# MCU.net
KiCad netlist of a schematic drawn in Altium Designer
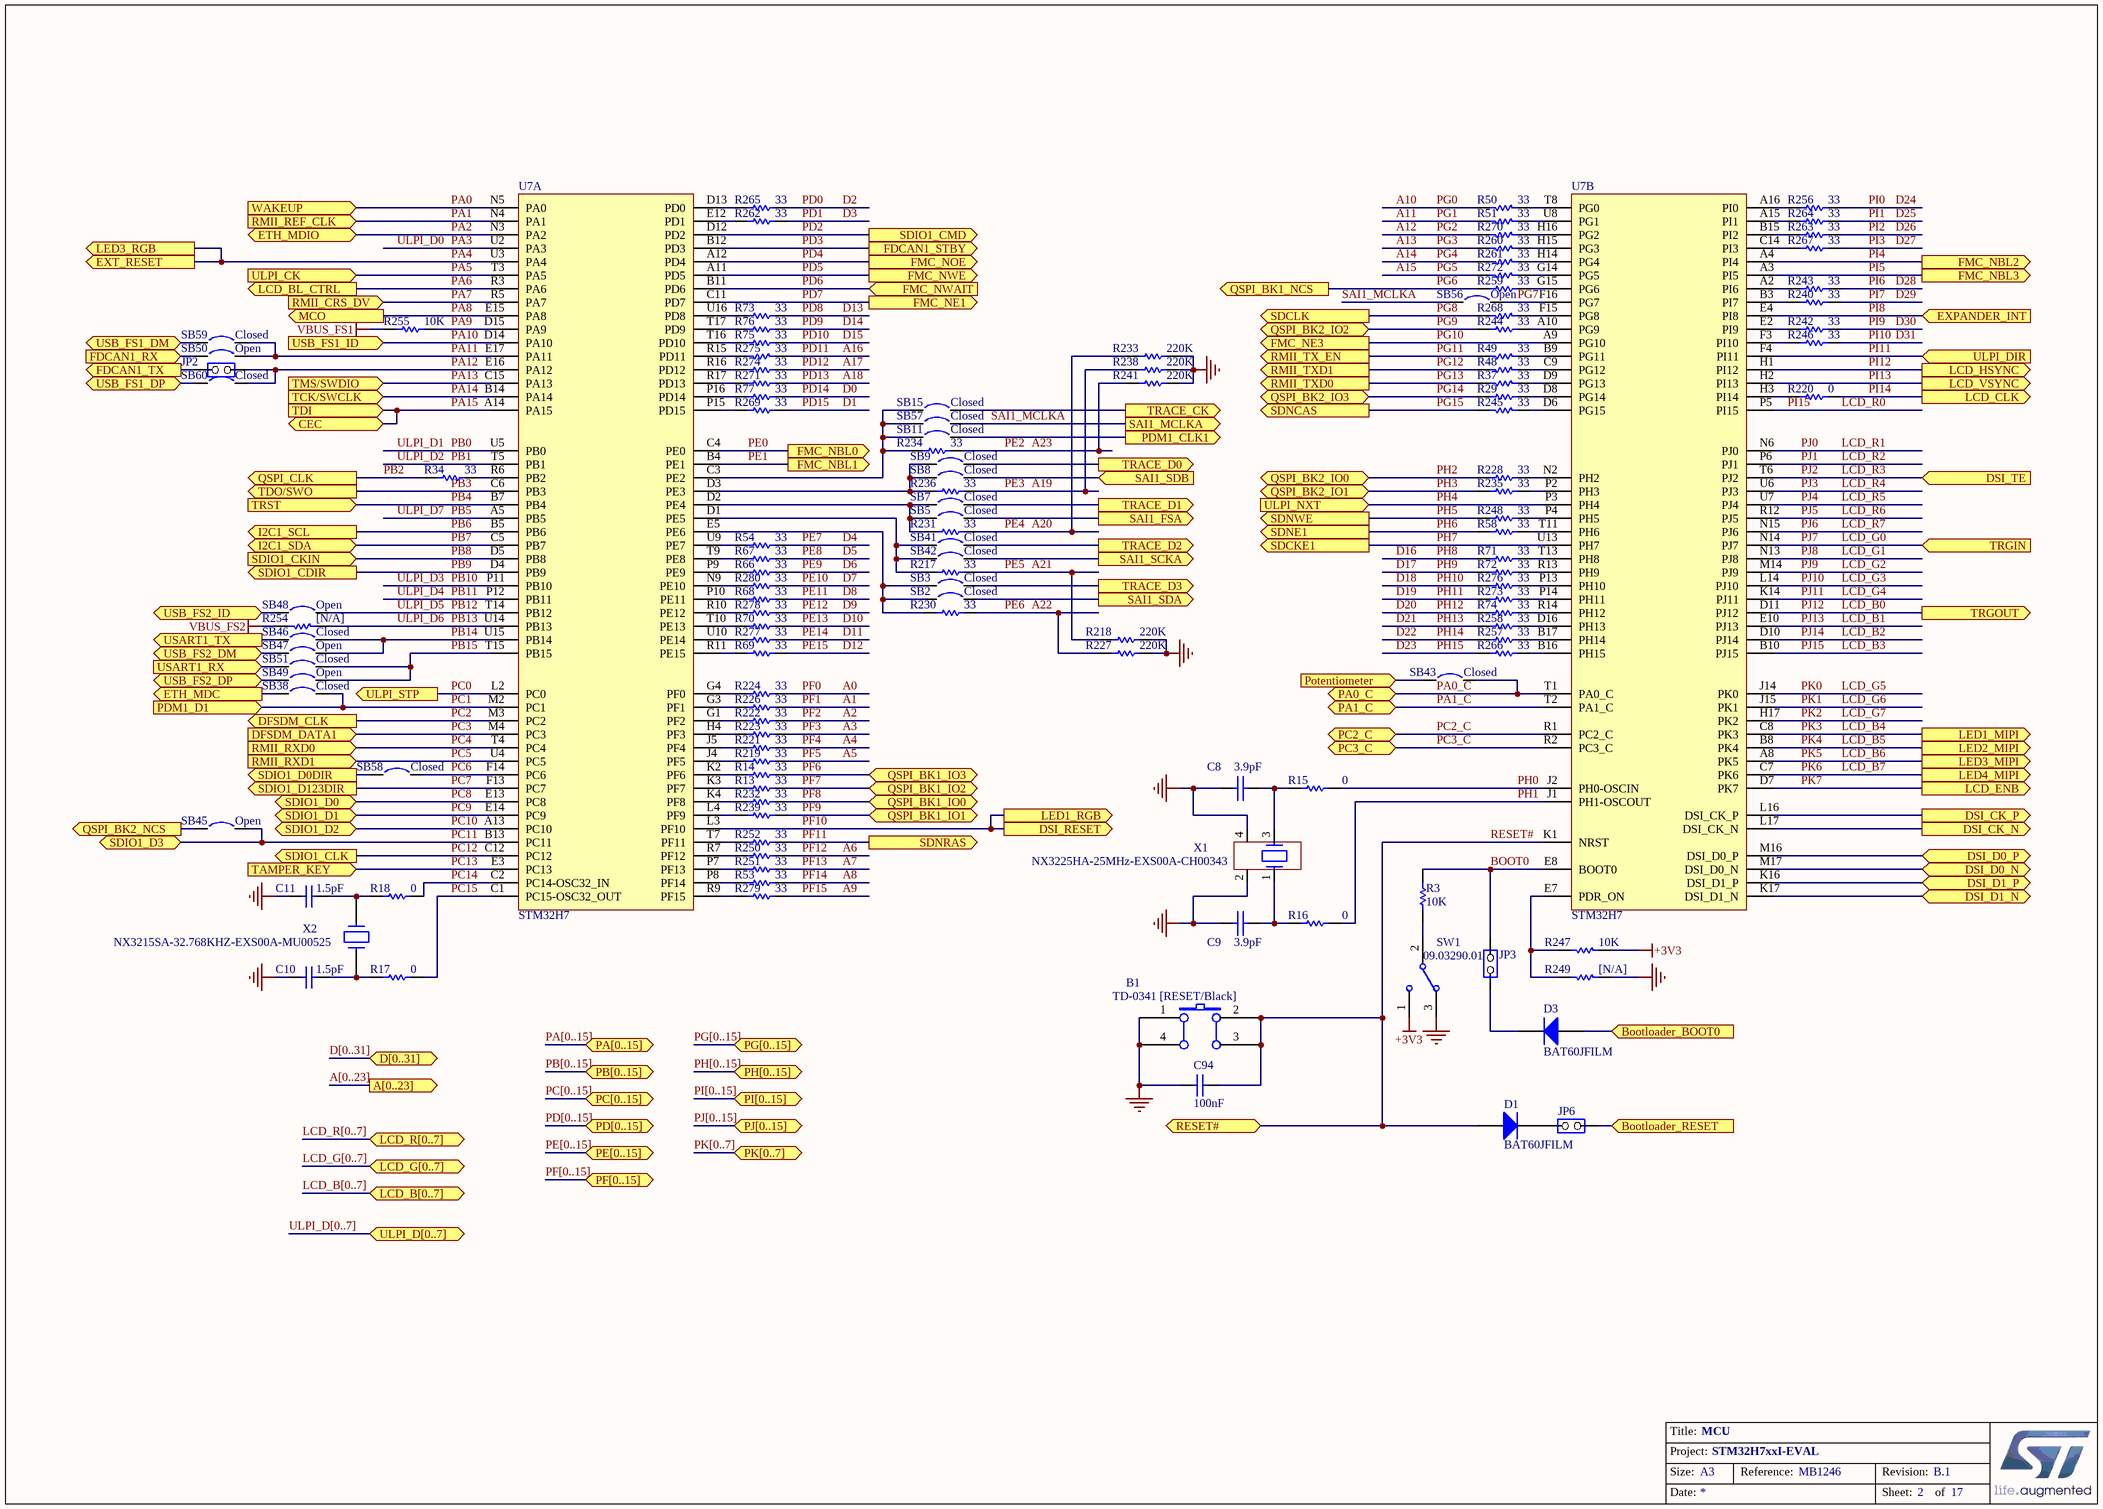
[diagram p0: MCU.SchDoc]

(export (version "E")
  (design (tool "Eeschema 10.0.6"))
  (components
    (comp (ref "B1")
      (value "TD-0341 [RESET/Black]")
      (footprint "PB10")
      (description "SE PUSHBUTTON")
      (libsource (lib "Documents") (part "SW PUSHBUTTON"))
    )
    (comp (ref "C8")
      (value "3.9pF")
      (footprint "0603C")
      (description "Capacitor")
      (libsource (lib "*") (part "CAP"))
    )
    (comp (ref "C9")
      (value "3.9pF")
      (footprint "0603C")
      (description "Capacitor")
      (libsource (lib "*") (part "CAP"))
    )
    (comp (ref "C10")
      (value "1.5pF")
      (footprint "0603C")
      (description "Capacitor 0402 / 0603 / 0805")
      (libsource (lib "MCD_TOOLS") (part "Capacitor_ST"))
    )
    (comp (ref "C11")
      (value "1.5pF")
      (footprint "0603C")
      (description "Capacitor 0402 / 0603 / 0805")
      (libsource (lib "MCD_TOOLS") (part "Capacitor_ST"))
    )
    (comp (ref "C94")
      (value "100nF")
      (footprint "0603C")
      (description "Capacitor")
      (fields (field (name "PUBLISHER") "Altium Limited"))
      (libsource (lib "Miscellaneous Devices") (part "CAP"))
    )
    (comp (ref "D1")
      (value "BAT60JFILM")
      (footprint "SOD-323")
      (description "Default Diode")
      (fields (field (name "PUBLISHER") "Altium Limited"))
      (libsource (lib "Miscellaneous Devices") (part "Diode"))
    )
    (comp (ref "D3")
      (value "BAT60JFILM")
      (footprint "SOD-323")
      (description "Default Diode")
      (fields (field (name "PUBLISHER") "Altium Limited"))
      (libsource (lib "Miscellaneous Devices") (part "Diode"))
    )
    (comp (ref "JP2") (value "~") (footprint "SIP2") (libsource (lib "*") (part "JP2")))
    (comp (ref "JP3") (value "~") (footprint "SIP2") (libsource (lib "*") (part "JP2")))
    (comp (ref "JP6") (value "~") (footprint "SIP2") (libsource (lib "*") (part "JP2")))
    (comp (ref "R3")
      (value "10K")
      (footprint "0603R")
      (description "Resistor")
      (fields (field (name "PUBLISHER") "Altium Limited"))
      (libsource (lib "Miscellaneous Devices") (part "res1"))
    )
    (comp (ref "R13")
      (value "33")
      (footprint "0402R")
      (description "Resistor")
      (fields (field (name "PUBLISHER") "Altium Limited"))
      (libsource (lib "Miscellaneous Devices") (part "Res1"))
    )
    (comp (ref "R14")
      (value "33")
      (footprint "0402R")
      (description "Resistor")
      (fields (field (name "PUBLISHER") "Altium Limited"))
      (libsource (lib "Miscellaneous Devices") (part "Res1"))
    )
    (comp (ref "R15")
      (value "0")
      (footprint "0603R")
      (description "Resistor")
      (fields (field (name "PUBLISHER") "Altium Limited"))
      (libsource (lib "") (part "Res1_1"))
    )
    (comp (ref "R16")
      (value "0")
      (footprint "0603R")
      (description "Resistor")
      (fields (field (name "PUBLISHER") "Altium Limited"))
      (libsource (lib "") (part "Res1_1"))
    )
    (comp (ref "R17")
      (value "0")
      (footprint "0402R")
      (description "Resistor")
      (fields (field (name "PUBLISHER") "Altium Limited"))
      (libsource (lib "Miscellaneous Devices") (part "Res1"))
    )
    (comp (ref "R18")
      (value "0")
      (footprint "0402R")
      (description "Resistor")
      (fields (field (name "PUBLISHER") "Altium Limited"))
      (libsource (lib "Miscellaneous Devices") (part "Res1"))
    )
    (comp (ref "R29")
      (value "33")
      (footprint "0402R")
      (description "Resistor")
      (fields (field (name "PUBLISHER") "Altium Limited"))
      (libsource (lib "Miscellaneous Devices") (part "Res1"))
    )
    (comp (ref "R34")
      (value "33")
      (footprint "0402R")
      (description "Resistor")
      (fields (field (name "PUBLISHER") "Altium Limited"))
      (libsource (lib "Miscellaneous Devices") (part "Res1"))
    )
    (comp (ref "R37")
      (value "33")
      (footprint "0603R")
      (description "Resistor")
      (fields (field (name "PUBLISHER") "Altium Limited"))
      (libsource (lib "Miscellaneous Devices") (part "Res1"))
    )
    (comp (ref "R48")
      (value "33")
      (footprint "0603R")
      (description "Resistor")
      (fields (field (name "PUBLISHER") "Altium Limited"))
      (libsource (lib "Miscellaneous Devices") (part "Res1"))
    )
    (comp (ref "R49")
      (value "33")
      (footprint "0603R")
      (description "Resistor")
      (fields (field (name "PUBLISHER") "Altium Limited"))
      (libsource (lib "Miscellaneous Devices") (part "Res1"))
    )
    (comp (ref "R50")
      (value "33")
      (footprint "0402R")
      (description "Resistor")
      (fields (field (name "PUBLISHER") "Altium Limited"))
      (libsource (lib "Miscellaneous Devices") (part "Res1"))
    )
    (comp (ref "R51")
      (value "33")
      (footprint "0402R")
      (description "Resistor")
      (fields (field (name "PUBLISHER") "Altium Limited"))
      (libsource (lib "Miscellaneous Devices") (part "Res1"))
    )
    (comp (ref "R53")
      (value "33")
      (footprint "0402R")
      (description "Resistor")
      (fields (field (name "PUBLISHER") "Altium Limited"))
      (libsource (lib "Miscellaneous Devices") (part "Res1"))
    )
    (comp (ref "R54")
      (value "33")
      (footprint "0402R")
      (description "Resistor")
      (fields (field (name "PUBLISHER") "Altium Limited"))
      (libsource (lib "Miscellaneous Devices") (part "Res1"))
    )
    (comp (ref "R58")
      (value "33")
      (footprint "0402R")
      (description "Resistor")
      (fields (field (name "PUBLISHER") "Altium Limited"))
      (libsource (lib "Miscellaneous Devices") (part "Res1"))
    )
    (comp (ref "R66")
      (value "33")
      (footprint "0402R")
      (description "Resistor")
      (fields (field (name "PUBLISHER") "Altium Limited"))
      (libsource (lib "Miscellaneous Devices") (part "Res1"))
    )
    (comp (ref "R67")
      (value "33")
      (footprint "0402R")
      (description "Resistor")
      (fields (field (name "PUBLISHER") "Altium Limited"))
      (libsource (lib "Miscellaneous Devices") (part "Res1"))
    )
    (comp (ref "R68")
      (value "33")
      (footprint "0402R")
      (description "Resistor")
      (fields (field (name "PUBLISHER") "Altium Limited"))
      (libsource (lib "Miscellaneous Devices") (part "Res1"))
    )
    (comp (ref "R69")
      (value "33")
      (footprint "0402R")
      (description "Resistor")
      (fields (field (name "PUBLISHER") "Altium Limited"))
      (libsource (lib "Miscellaneous Devices") (part "Res1"))
    )
    (comp (ref "R70")
      (value "33")
      (footprint "0402R")
      (description "Resistor")
      (fields (field (name "PUBLISHER") "Altium Limited"))
      (libsource (lib "Miscellaneous Devices") (part "Res1"))
    )
    (comp (ref "R71")
      (value "33")
      (footprint "0402R")
      (description "Resistor")
      (fields (field (name "PUBLISHER") "Altium Limited"))
      (libsource (lib "Miscellaneous Devices") (part "Res1"))
    )
    (comp (ref "R72")
      (value "33")
      (footprint "0402R")
      (description "Resistor")
      (fields (field (name "PUBLISHER") "Altium Limited"))
      (libsource (lib "Miscellaneous Devices") (part "Res1"))
    )
    (comp (ref "R73")
      (value "33")
      (footprint "0402R")
      (description "Resistor")
      (fields (field (name "PUBLISHER") "Altium Limited"))
      (libsource (lib "Miscellaneous Devices") (part "Res1"))
    )
    (comp (ref "R74")
      (value "33")
      (footprint "0402R")
      (description "Resistor")
      (fields (field (name "PUBLISHER") "Altium Limited"))
      (libsource (lib "Miscellaneous Devices") (part "Res1"))
    )
    (comp (ref "R75")
      (value "33")
      (footprint "0402R")
      (description "Resistor")
      (fields (field (name "PUBLISHER") "Altium Limited"))
      (libsource (lib "Miscellaneous Devices") (part "Res1"))
    )
    (comp (ref "R76")
      (value "33")
      (footprint "0402R")
      (description "Resistor")
      (fields (field (name "PUBLISHER") "Altium Limited"))
      (libsource (lib "Miscellaneous Devices") (part "Res1"))
    )
    (comp (ref "R77")
      (value "33")
      (footprint "0402R")
      (description "Resistor")
      (fields (field (name "PUBLISHER") "Altium Limited"))
      (libsource (lib "Miscellaneous Devices") (part "Res1"))
    )
    (comp (ref "R217")
      (value "33")
      (footprint "0402R")
      (description "Resistor")
      (fields (field (name "PUBLISHER") "Altium Limited"))
      (libsource (lib "Miscellaneous Devices") (part "Res1"))
    )
    (comp (ref "R218")
      (value "220K")
      (footprint "0603R")
      (description "Resistor")
      (fields (field (name "PUBLISHER") "Altium Limited"))
      (libsource (lib "Miscellaneous Devices") (part "res1"))
    )
    (comp (ref "R219")
      (value "33")
      (footprint "0402R")
      (description "Resistor")
      (fields (field (name "PUBLISHER") "Altium Limited"))
      (libsource (lib "Miscellaneous Devices") (part "Res1"))
    )
    (comp (ref "R220")
      (value "0")
      (footprint "0603R")
      (description "Resistor")
      (fields (field (name "PUBLISHER") "Altium Limited"))
      (libsource (lib "Miscellaneous Devices") (part "Res1"))
    )
    (comp (ref "R221")
      (value "33")
      (footprint "0402R")
      (description "Resistor")
      (fields (field (name "PUBLISHER") "Altium Limited"))
      (libsource (lib "Miscellaneous Devices") (part "Res1"))
    )
    (comp (ref "R222")
      (value "33")
      (footprint "0402R")
      (description "Resistor")
      (fields (field (name "PUBLISHER") "Altium Limited"))
      (libsource (lib "Miscellaneous Devices") (part "Res1"))
    )
    (comp (ref "R223")
      (value "33")
      (footprint "0402R")
      (description "Resistor")
      (fields (field (name "PUBLISHER") "Altium Limited"))
      (libsource (lib "Miscellaneous Devices") (part "Res1"))
    )
    (comp (ref "R224")
      (value "33")
      (footprint "0402R")
      (description "Resistor")
      (fields (field (name "PUBLISHER") "Altium Limited"))
      (libsource (lib "Miscellaneous Devices") (part "Res1"))
    )
    (comp (ref "R226")
      (value "33")
      (footprint "0402R")
      (description "Resistor")
      (fields (field (name "PUBLISHER") "Altium Limited"))
      (libsource (lib "Miscellaneous Devices") (part "Res1"))
    )
    (comp (ref "R227")
      (value "220K")
      (footprint "0603R")
      (description "Resistor")
      (fields (field (name "PUBLISHER") "Altium Limited"))
      (libsource (lib "Miscellaneous Devices") (part "res1"))
    )
    (comp (ref "R228")
      (value "33")
      (footprint "0402R")
      (description "Resistor")
      (fields (field (name "PUBLISHER") "Altium Limited"))
      (libsource (lib "Miscellaneous Devices") (part "Res1"))
    )
    (comp (ref "R230")
      (value "33")
      (footprint "0402R")
      (description "Resistor")
      (fields (field (name "PUBLISHER") "Altium Limited"))
      (libsource (lib "Miscellaneous Devices") (part "Res1"))
    )
    (comp (ref "R231")
      (value "33")
      (footprint "0402R")
      (description "Resistor")
      (fields (field (name "PUBLISHER") "Altium Limited"))
      (libsource (lib "Miscellaneous Devices") (part "Res1"))
    )
    (comp (ref "R232")
      (value "33")
      (footprint "0402R")
      (description "Resistor")
      (fields (field (name "PUBLISHER") "Altium Limited"))
      (libsource (lib "Miscellaneous Devices") (part "Res1"))
    )
    (comp (ref "R233")
      (value "220K")
      (footprint "0603R")
      (description "Resistor")
      (fields (field (name "PUBLISHER") "Altium Limited"))
      (libsource (lib "Miscellaneous Devices") (part "res1"))
    )
    (comp (ref "R234")
      (value "33")
      (footprint "0402R")
      (description "Resistor")
      (fields (field (name "PUBLISHER") "Altium Limited"))
      (libsource (lib "Miscellaneous Devices") (part "Res1"))
    )
    (comp (ref "R235")
      (value "33")
      (footprint "0402R")
      (description "Resistor")
      (fields (field (name "PUBLISHER") "Altium Limited"))
      (libsource (lib "Miscellaneous Devices") (part "Res1"))
    )
    (comp (ref "R236")
      (value "33")
      (footprint "0402R")
      (description "Resistor")
      (fields (field (name "PUBLISHER") "Altium Limited"))
      (libsource (lib "Miscellaneous Devices") (part "Res1"))
    )
    (comp (ref "R238")
      (value "220K")
      (footprint "0603R")
      (description "Resistor")
      (fields (field (name "PUBLISHER") "Altium Limited"))
      (libsource (lib "Miscellaneous Devices") (part "res1"))
    )
    (comp (ref "R239")
      (value "33")
      (footprint "0402R")
      (description "Resistor")
      (fields (field (name "PUBLISHER") "Altium Limited"))
      (libsource (lib "Miscellaneous Devices") (part "Res1"))
    )
    (comp (ref "R240")
      (value "33")
      (footprint "0402R")
      (description "Resistor")
      (fields (field (name "PUBLISHER") "Altium Limited"))
      (libsource (lib "Miscellaneous Devices") (part "Res1"))
    )
    (comp (ref "R241")
      (value "220K")
      (footprint "0603R")
      (description "Resistor")
      (fields (field (name "PUBLISHER") "Altium Limited"))
      (libsource (lib "Miscellaneous Devices") (part "res1"))
    )
    (comp (ref "R242")
      (value "33")
      (footprint "0402R")
      (description "Resistor")
      (fields (field (name "PUBLISHER") "Altium Limited"))
      (libsource (lib "Miscellaneous Devices") (part "Res1"))
    )
    (comp (ref "R243")
      (value "33")
      (footprint "0402R")
      (description "Resistor")
      (fields (field (name "PUBLISHER") "Altium Limited"))
      (libsource (lib "Miscellaneous Devices") (part "Res1"))
    )
    (comp (ref "R244")
      (value "33")
      (footprint "0402R")
      (description "Resistor")
      (fields (field (name "PUBLISHER") "Altium Limited"))
      (libsource (lib "Miscellaneous Devices") (part "Res1"))
    )
    (comp (ref "R245")
      (value "33")
      (footprint "0402R")
      (description "Resistor")
      (fields (field (name "PUBLISHER") "Altium Limited"))
      (libsource (lib "Miscellaneous Devices") (part "Res1"))
    )
    (comp (ref "R246")
      (value "33")
      (footprint "0402R")
      (description "Resistor")
      (fields (field (name "PUBLISHER") "Altium Limited"))
      (libsource (lib "Miscellaneous Devices") (part "Res1"))
    )
    (comp (ref "R247")
      (value "10K")
      (footprint "0603R")
      (description "Resistor")
      (fields (field (name "PUBLISHER") "Altium Limited"))
      (libsource (lib "Miscellaneous Devices") (part "Res1"))
    )
    (comp (ref "R248")
      (value "33")
      (footprint "0402R")
      (description "Resistor")
      (fields (field (name "PUBLISHER") "Altium Limited"))
      (libsource (lib "Miscellaneous Devices") (part "Res1"))
    )
    (comp (ref "R249")
      (value "[N/A]")
      (footprint "0603R")
      (description "Resistor")
      (fields (field (name "PUBLISHER") "Altium Limited"))
      (libsource (lib "Miscellaneous Devices") (part "Res1"))
    )
    (comp (ref "R250")
      (value "33")
      (footprint "0402R")
      (description "Resistor")
      (fields (field (name "PUBLISHER") "Altium Limited"))
      (libsource (lib "Miscellaneous Devices") (part "Res1"))
    )
    (comp (ref "R251")
      (value "33")
      (footprint "0402R")
      (description "Resistor")
      (fields (field (name "PUBLISHER") "Altium Limited"))
      (libsource (lib "Miscellaneous Devices") (part "Res1"))
    )
    (comp (ref "R252")
      (value "33")
      (footprint "0402R")
      (description "Resistor")
      (fields (field (name "PUBLISHER") "Altium Limited"))
      (libsource (lib "Miscellaneous Devices") (part "Res1"))
    )
    (comp (ref "R254")
      (value "[N/A]")
      (footprint "0603R")
      (description "Resistor")
      (fields (field (name "PUBLISHER") "Altium Limited"))
      (libsource (lib "Miscellaneous Devices") (part "Res1"))
    )
    (comp (ref "R255")
      (value "10K")
      (footprint "0603R")
      (description "Resistor")
      (fields (field (name "PUBLISHER") "Altium Limited"))
      (libsource (lib "Miscellaneous Devices") (part "Res1"))
    )
    (comp (ref "R256")
      (value "33")
      (footprint "0402R")
      (description "Resistor")
      (fields (field (name "PUBLISHER") "Altium Limited"))
      (libsource (lib "Miscellaneous Devices") (part "Res1"))
    )
    (comp (ref "R257")
      (value "33")
      (footprint "0402R")
      (description "Resistor")
      (fields (field (name "PUBLISHER") "Altium Limited"))
      (libsource (lib "Miscellaneous Devices") (part "Res1"))
    )
    (comp (ref "R258")
      (value "33")
      (footprint "0402R")
      (description "Resistor")
      (fields (field (name "PUBLISHER") "Altium Limited"))
      (libsource (lib "Miscellaneous Devices") (part "Res1"))
    )
    (comp (ref "R259")
      (value "33")
      (footprint "0402R")
      (description "Resistor")
      (fields (field (name "PUBLISHER") "Altium Limited"))
      (libsource (lib "Miscellaneous Devices") (part "Res1"))
    )
    (comp (ref "R260")
      (value "33")
      (footprint "0402R")
      (description "Resistor")
      (fields (field (name "PUBLISHER") "Altium Limited"))
      (libsource (lib "Miscellaneous Devices") (part "Res1"))
    )
    (comp (ref "R261")
      (value "33")
      (footprint "0402R")
      (description "Resistor")
      (fields (field (name "PUBLISHER") "Altium Limited"))
      (libsource (lib "Miscellaneous Devices") (part "Res1"))
    )
    (comp (ref "R262")
      (value "33")
      (footprint "0402R")
      (description "Resistor")
      (fields (field (name "PUBLISHER") "Altium Limited"))
      (libsource (lib "Miscellaneous Devices") (part "Res1"))
    )
    (comp (ref "R263")
      (value "33")
      (footprint "0402R")
      (description "Resistor")
      (fields (field (name "PUBLISHER") "Altium Limited"))
      (libsource (lib "Miscellaneous Devices") (part "Res1"))
    )
    (comp (ref "R264")
      (value "33")
      (footprint "0402R")
      (description "Resistor")
      (fields (field (name "PUBLISHER") "Altium Limited"))
      (libsource (lib "Miscellaneous Devices") (part "Res1"))
    )
    (comp (ref "R265")
      (value "33")
      (footprint "0402R")
      (description "Resistor")
      (fields (field (name "PUBLISHER") "Altium Limited"))
      (libsource (lib "Miscellaneous Devices") (part "Res1"))
    )
    (comp (ref "R266")
      (value "33")
      (footprint "0402R")
      (description "Resistor")
      (fields (field (name "PUBLISHER") "Altium Limited"))
      (libsource (lib "Miscellaneous Devices") (part "Res1"))
    )
    (comp (ref "R267")
      (value "33")
      (footprint "0402R")
      (description "Resistor")
      (fields (field (name "PUBLISHER") "Altium Limited"))
      (libsource (lib "Miscellaneous Devices") (part "Res1"))
    )
    (comp (ref "R268")
      (value "33")
      (footprint "0402R")
      (description "Resistor")
      (fields (field (name "PUBLISHER") "Altium Limited"))
      (libsource (lib "Miscellaneous Devices") (part "Res1"))
    )
    (comp (ref "R269")
      (value "33")
      (footprint "0402R")
      (description "Resistor")
      (fields (field (name "PUBLISHER") "Altium Limited"))
      (libsource (lib "Miscellaneous Devices") (part "Res1"))
    )
    (comp (ref "R270")
      (value "33")
      (footprint "0402R")
      (description "Resistor")
      (fields (field (name "PUBLISHER") "Altium Limited"))
      (libsource (lib "Miscellaneous Devices") (part "Res1"))
    )
    (comp (ref "R271")
      (value "33")
      (footprint "0402R")
      (description "Resistor")
      (fields (field (name "PUBLISHER") "Altium Limited"))
      (libsource (lib "Miscellaneous Devices") (part "Res1"))
    )
    (comp (ref "R272")
      (value "33")
      (footprint "0402R")
      (description "Resistor")
      (fields (field (name "PUBLISHER") "Altium Limited"))
      (libsource (lib "Miscellaneous Devices") (part "Res1"))
    )
    (comp (ref "R273")
      (value "33")
      (footprint "0402R")
      (description "Resistor")
      (fields (field (name "PUBLISHER") "Altium Limited"))
      (libsource (lib "Miscellaneous Devices") (part "Res1"))
    )
    (comp (ref "R274")
      (value "33")
      (footprint "0402R")
      (description "Resistor")
      (fields (field (name "PUBLISHER") "Altium Limited"))
      (libsource (lib "Miscellaneous Devices") (part "Res1"))
    )
    (comp (ref "R275")
      (value "33")
      (footprint "0402R")
      (description "Resistor")
      (fields (field (name "PUBLISHER") "Altium Limited"))
      (libsource (lib "Miscellaneous Devices") (part "Res1"))
    )
    (comp (ref "R276")
      (value "33")
      (footprint "0402R")
      (description "Resistor")
      (fields (field (name "PUBLISHER") "Altium Limited"))
      (libsource (lib "Miscellaneous Devices") (part "Res1"))
    )
    (comp (ref "R277")
      (value "33")
      (footprint "0402R")
      (description "Resistor")
      (fields (field (name "PUBLISHER") "Altium Limited"))
      (libsource (lib "Miscellaneous Devices") (part "Res1"))
    )
    (comp (ref "R278")
      (value "33")
      (footprint "0402R")
      (description "Resistor")
      (fields (field (name "PUBLISHER") "Altium Limited"))
      (libsource (lib "Miscellaneous Devices") (part "Res1"))
    )
    (comp (ref "R279")
      (value "33")
      (footprint "0402R")
      (description "Resistor")
      (fields (field (name "PUBLISHER") "Altium Limited"))
      (libsource (lib "Miscellaneous Devices") (part "Res1"))
    )
    (comp (ref "R280")
      (value "33")
      (footprint "0402R")
      (description "Resistor")
      (fields (field (name "PUBLISHER") "Altium Limited"))
      (libsource (lib "Miscellaneous Devices") (part "Res1"))
    )
    (comp (ref "SB2")
      (value "Closed")
      (footprint "SB_0603")
      (description "Circuit Breaker")
      (fields (field (name "PUBLISHER") "Altium Limited"))
      (libsource (lib "MB1165") (part "Circuit Breaker_close"))
    )
    (comp (ref "SB3")
      (value "Closed")
      (footprint "SB_0603")
      (description "Circuit Breaker")
      (fields (field (name "PUBLISHER") "Altium Limited"))
      (libsource (lib "MB1165") (part "Circuit Breaker_close"))
    )
    (comp (ref "SB5")
      (value "Closed")
      (footprint "SB_0603")
      (description "Circuit Breaker")
      (fields (field (name "PUBLISHER") "Altium Limited"))
      (libsource (lib "MB1165") (part "Circuit Breaker_close"))
    )
    (comp (ref "SB7")
      (value "Closed")
      (footprint "SB_0603")
      (description "Circuit Breaker")
      (fields (field (name "PUBLISHER") "Altium Limited"))
      (libsource (lib "MB1165") (part "Circuit Breaker_close"))
    )
    (comp (ref "SB8")
      (value "Closed")
      (footprint "SB_0603")
      (description "Circuit Breaker")
      (fields (field (name "PUBLISHER") "Altium Limited"))
      (libsource (lib "MB1165") (part "Circuit Breaker_close"))
    )
    (comp (ref "SB9")
      (value "Closed")
      (footprint "SB_0603")
      (description "Circuit Breaker")
      (fields (field (name "PUBLISHER") "Altium Limited"))
      (libsource (lib "MB1165") (part "Circuit Breaker_close"))
    )
    (comp (ref "SB11")
      (value "Closed")
      (footprint "SB_0603")
      (description "Circuit Breaker")
      (fields (field (name "PUBLISHER") "Altium Limited"))
      (libsource (lib "MB1165") (part "Circuit Breaker_close"))
    )
    (comp (ref "SB15")
      (value "Closed")
      (footprint "SB_0603")
      (description "Circuit Breaker")
      (fields (field (name "PUBLISHER") "Altium Limited"))
      (libsource (lib "MB1165") (part "Circuit Breaker_close"))
    )
    (comp (ref "SB38")
      (value "Closed")
      (footprint "SB_0603")
      (description "Circuit Breaker")
      (fields (field (name "PUBLISHER") "Altium Limited"))
      (libsource (lib "") (part "Circuit Breaker_close_1"))
    )
    (comp (ref "SB41")
      (value "Closed")
      (footprint "SB_0603")
      (description "Circuit Breaker")
      (fields (field (name "PUBLISHER") "Altium Limited"))
      (libsource (lib "MB1165") (part "Circuit Breaker_close"))
    )
    (comp (ref "SB42")
      (value "Closed")
      (footprint "SB_0603")
      (description "Circuit Breaker")
      (fields (field (name "PUBLISHER") "Altium Limited"))
      (libsource (lib "MB1165") (part "Circuit Breaker_close"))
    )
    (comp (ref "SB43")
      (value "Closed")
      (footprint "SB_0603")
      (description "Circuit Breaker")
      (fields (field (name "PUBLISHER") "Altium Limited"))
      (libsource (lib "MB1165") (part "Circuit Breaker_close"))
    )
    (comp (ref "SB45")
      (value "Open")
      (footprint "SB_0603")
      (description "Circuit Breaker")
      (fields (field (name "PUBLISHER") "Altium Limited"))
      (libsource (lib "MB1165") (part "Circuit Breaker"))
    )
    (comp (ref "SB46")
      (value "Closed")
      (footprint "SB_0603")
      (description "Circuit Breaker")
      (fields (field (name "PUBLISHER") "Altium Limited"))
      (libsource (lib "") (part "Circuit Breaker_close_1"))
    )
    (comp (ref "SB47")
      (value "Open")
      (footprint "SB_0603")
      (description "Circuit Breaker")
      (fields (field (name "PUBLISHER") "Altium Limited"))
      (libsource (lib "MB1165") (part "Circuit Breaker"))
    )
    (comp (ref "SB48")
      (value "Open")
      (footprint "SB_0603")
      (description "Circuit Breaker")
      (fields (field (name "PUBLISHER") "Altium Limited"))
      (libsource (lib "MB1165") (part "Circuit Breaker"))
    )
    (comp (ref "SB49")
      (value "Open")
      (footprint "SB_0603")
      (description "Circuit Breaker")
      (fields (field (name "PUBLISHER") "Altium Limited"))
      (libsource (lib "MB1165") (part "Circuit Breaker"))
    )
    (comp (ref "SB50")
      (value "Open")
      (footprint "SB_0603")
      (description "Circuit Breaker")
      (fields (field (name "PUBLISHER") "Altium Limited"))
      (libsource (lib "MB1165") (part "Circuit Breaker"))
    )
    (comp (ref "SB51")
      (value "Closed")
      (footprint "SB_0603")
      (description "Circuit Breaker")
      (fields (field (name "PUBLISHER") "Altium Limited"))
      (libsource (lib "") (part "Circuit Breaker_close_1"))
    )
    (comp (ref "SB56")
      (value "Open")
      (footprint "SB_0603")
      (description "Circuit Breaker")
      (fields (field (name "PUBLISHER") "Altium Limited"))
      (libsource (lib "MB1165") (part "Circuit Breaker"))
    )
    (comp (ref "SB57")
      (value "Closed")
      (footprint "SB_0603")
      (description "Circuit Breaker")
      (fields (field (name "PUBLISHER") "Altium Limited"))
      (libsource (lib "MB1165") (part "Circuit Breaker_close"))
    )
    (comp (ref "SB58")
      (value "Closed")
      (footprint "SB_0603")
      (description "Circuit Breaker")
      (fields (field (name "PUBLISHER") "Altium Limited"))
      (libsource (lib "MB1165") (part "Circuit Breaker_close"))
    )
    (comp (ref "SB59")
      (value "Closed")
      (footprint "SB_0603")
      (description "Circuit Breaker")
      (fields (field (name "PUBLISHER") "Altium Limited"))
      (libsource (lib "") (part "Circuit Breaker_close_1"))
    )
    (comp (ref "SB60")
      (value "Closed")
      (footprint "SB_0603")
      (description "Circuit Breaker")
      (fields (field (name "PUBLISHER") "Altium Limited"))
      (libsource (lib "") (part "Circuit Breaker_close_1"))
    )
    (comp (ref "SW1")
      (value "09.03290.01")
      (footprint "SW1_3TH_2R54_10X2R5")
      (description "SPDT Subminiature Toggle Switch, Right Angle Mounting, Vertical Actuation")
      (fields (field (name "PUBLISHER") "Altium Limited"))
      (libsource (lib "mb1045") (part "SW-SPDT"))
    )
    (comp (ref "U7")
      (value "STM32H7")
      (footprint "BGA265_0R8_14X14_SKT")
      (libsource (lib "MB1246") (part "STM32H7_TFBGA265"))
    )
    (comp (ref "X1")
      (value "NX3225HA-25MHz-EXS00A-CH00343")
      (footprint "XTAL_4SM_3R2X2R5")
      (libsource (lib "MB1246") (part "NX3225HA-25MHz-EXS00A-CH00343"))
    )
    (comp (ref "X2")
      (value "NX3215SA-32.768KHZ-EXS00A-MU00525")
      (footprint "XTAL_2SM_3R2X1R5")
      (description "Crystal")
      (libsource (lib "MB1167") (part "CRYSTAL_32K"))
    )
  )
  (nets
    (net (code "1") (name "+3V3") (class "Default")
      (node (ref "R247") (pin "1") (pinfunction "1_1") (pintype "passive"))
      (node (ref "SW1") (pin "1") (pintype "passive"))
    )
    (net (code "2") (name "/A10") (class "Default")
      (node (ref "R50") (pin "1") (pinfunction "1_1") (pintype "passive"))
    )
    (net (code "3") (name "/A11") (class "Default")
      (node (ref "R51") (pin "1") (pinfunction "1_1") (pintype "passive"))
    )
    (net (code "4") (name "/A12") (class "Default")
      (node (ref "R270") (pin "1") (pinfunction "1_1") (pintype "passive"))
    )
    (net (code "5") (name "/A13") (class "Default")
      (node (ref "R260") (pin "1") (pinfunction "1_1") (pintype "passive"))
    )
    (net (code "6") (name "/A14") (class "Default")
      (node (ref "R261") (pin "1") (pinfunction "1_1") (pintype "passive"))
    )
    (net (code "7") (name "/A15") (class "Default")
      (node (ref "R272") (pin "1") (pinfunction "1_1") (pintype "passive"))
    )
    (net (code "9") (name "/BOOT0") (class "Default")
      (node (ref "JP3") (pin "2") (pinfunction "NO_2") (pintype "passive"))
      (node (ref "R3") (pin "1") (pinfunction "1_1") (pintype "passive"))
      (node (ref "U7") (pin "E8") (pinfunction "BOOT0_E8") (pintype "passive"))
    )
    (net (code "10") (name "/Bootloader_BOOT0") (class "Default")
      (node (ref "D3") (pin "1") (pinfunction "A_1") (pintype "passive"))
    )
    (net (code "11") (name "/Bootloader_RESET") (class "Default")
      (node (ref "JP6") (pin "2") (pinfunction "NO_2") (pintype "passive"))
    )
    (net (code "12") (name "/D16") (class "Default")
      (node (ref "R71") (pin "2") (pinfunction "2_2") (pintype "passive"))
    )
    (net (code "13") (name "/D17") (class "Default")
      (node (ref "R72") (pin "2") (pinfunction "2_2") (pintype "passive"))
    )
    (net (code "14") (name "/D18") (class "Default")
      (node (ref "R276") (pin "2") (pinfunction "2_2") (pintype "passive"))
    )
    (net (code "15") (name "/D19") (class "Default")
      (node (ref "R273") (pin "2") (pinfunction "2_2") (pintype "passive"))
    )
    (net (code "16") (name "/D20") (class "Default")
      (node (ref "R74") (pin "2") (pinfunction "2_2") (pintype "passive"))
    )
    (net (code "17") (name "/D21") (class "Default")
      (node (ref "R258") (pin "2") (pinfunction "2_2") (pintype "passive"))
    )
    (net (code "18") (name "/D22") (class "Default")
      (node (ref "R257") (pin "2") (pinfunction "2_2") (pintype "passive"))
    )
    (net (code "19") (name "/D23") (class "Default")
      (node (ref "R266") (pin "2") (pinfunction "2_2") (pintype "passive"))
    )
    (net (code "20") (name "/D24") (class "Default")
      (node (ref "R256") (pin "1") (pinfunction "1_1") (pintype "passive"))
    )
    (net (code "21") (name "/D25") (class "Default")
      (node (ref "R264") (pin "1") (pinfunction "1_1") (pintype "passive"))
    )
    (net (code "22") (name "/D26") (class "Default")
      (node (ref "R263") (pin "1") (pinfunction "1_1") (pintype "passive"))
    )
    (net (code "23") (name "/D27") (class "Default")
      (node (ref "R267") (pin "1") (pinfunction "1_1") (pintype "passive"))
    )
    (net (code "24") (name "/D28") (class "Default")
      (node (ref "R243") (pin "1") (pinfunction "1_1") (pintype "passive"))
    )
    (net (code "25") (name "/D29") (class "Default")
      (node (ref "R240") (pin "1") (pinfunction "1_1") (pintype "passive"))
    )
    (net (code "26") (name "/D30") (class "Default")
      (node (ref "R242") (pin "1") (pinfunction "1_1") (pintype "passive"))
    )
    (net (code "27") (name "/D31") (class "Default")
      (node (ref "R246") (pin "1") (pinfunction "1_1") (pintype "passive"))
    )
    (net (code "28") (name "/DSI_CK_N") (class "Default")
      (node (ref "U7") (pin "L17") (pinfunction "DSI_CK_N_L17") (pintype "passive"))
    )
    (net (code "29") (name "/DSI_CK_P") (class "Default")
      (node (ref "U7") (pin "L16") (pinfunction "DSI_CK_P_L16") (pintype "passive"))
    )
    (net (code "30") (name "/DSI_D0_N") (class "Default")
      (node (ref "U7") (pin "M17") (pinfunction "DSI_D0_N_M17") (pintype "passive"))
    )
    (net (code "31") (name "/DSI_D0_P") (class "Default")
      (node (ref "U7") (pin "M16") (pinfunction "DSI_D0_P_M16") (pintype "passive"))
    )
    (net (code "32") (name "/DSI_D1_N") (class "Default")
      (node (ref "U7") (pin "K17") (pinfunction "DSI_D1_N_K17") (pintype "passive"))
    )
    (net (code "33") (name "/DSI_D1_P") (class "Default")
      (node (ref "U7") (pin "K16") (pinfunction "DSI_D1_P_K16") (pintype "passive"))
    )
    (net (code "35") (name "/ETH_MDC") (class "Default")
      (node (ref "SB38") (pin "1") (pinfunction "1_1") (pintype "passive"))
    )
    (net (code "36") (name "/FDCAN1_RX") (class "Default")
      (node (ref "SB50") (pin "1") (pinfunction "1_1") (pintype "passive"))
    )
    (net (code "37") (name "/FDCAN1_TX") (class "Default")
      (node (ref "JP2") (pin "2") (pinfunction "NO_2") (pintype "passive"))
    )
    (net (code "38") (name "/LCD_B0") (class "Default")
      (node (ref "U7") (pin "D11") (pinfunction "PJ12_D11") (pintype "passive"))
    )
    (net (code "39") (name "/LCD_B1") (class "Default")
      (node (ref "U7") (pin "E10") (pinfunction "PJ13_E10") (pintype "passive"))
    )
    (net (code "40") (name "/LCD_B2") (class "Default")
      (node (ref "U7") (pin "D10") (pinfunction "PJ14_D10") (pintype "passive"))
    )
    (net (code "41") (name "/LCD_B3") (class "Default")
      (node (ref "U7") (pin "B10") (pinfunction "PJ15_B10") (pintype "passive"))
    )
    (net (code "42") (name "/LCD_B4") (class "Default")
      (node (ref "U7") (pin "C8") (pinfunction "PK3_C8") (pintype "passive"))
    )
    (net (code "43") (name "/LCD_B5") (class "Default")
      (node (ref "U7") (pin "B8") (pinfunction "PK4_B8") (pintype "passive"))
    )
    (net (code "44") (name "/LCD_B6") (class "Default")
      (node (ref "U7") (pin "A8") (pinfunction "PK5_A8") (pintype "passive"))
    )
    (net (code "45") (name "/LCD_B7") (class "Default")
      (node (ref "U7") (pin "C7") (pinfunction "PK6_C7") (pintype "passive"))
    )
    (net (code "47") (name "/LCD_G0") (class "Default")
      (node (ref "U7") (pin "N14") (pinfunction "PJ7_N14") (pintype "passive"))
    )
    (net (code "48") (name "/LCD_G1") (class "Default")
      (node (ref "U7") (pin "N13") (pinfunction "PJ8_N13") (pintype "passive"))
    )
    (net (code "49") (name "/LCD_G2") (class "Default")
      (node (ref "U7") (pin "M14") (pinfunction "PJ9_M14") (pintype "passive"))
    )
    (net (code "50") (name "/LCD_G3") (class "Default")
      (node (ref "U7") (pin "L14") (pinfunction "PJ10_L14") (pintype "passive"))
    )
    (net (code "51") (name "/LCD_G4") (class "Default")
      (node (ref "U7") (pin "K14") (pinfunction "PJ11_K14") (pintype "passive"))
    )
    (net (code "52") (name "/LCD_G5") (class "Default")
      (node (ref "U7") (pin "J14") (pinfunction "PK0_J14") (pintype "passive"))
    )
    (net (code "53") (name "/LCD_G6") (class "Default")
      (node (ref "U7") (pin "J15") (pinfunction "PK1_J15") (pintype "passive"))
    )
    (net (code "54") (name "/LCD_G7") (class "Default")
      (node (ref "U7") (pin "H17") (pinfunction "PK2_H17") (pintype "passive"))
    )
    (net (code "56") (name "/LCD_R0") (class "Default")
      (node (ref "U7") (pin "P5") (pinfunction "PI15_P5") (pintype "passive"))
    )
    (net (code "57") (name "/LCD_R1") (class "Default")
      (node (ref "U7") (pin "N6") (pinfunction "PJ0_N6") (pintype "passive"))
    )
    (net (code "58") (name "/LCD_R2") (class "Default")
      (node (ref "U7") (pin "P6") (pinfunction "PJ1_P6") (pintype "passive"))
    )
    (net (code "59") (name "/LCD_R3") (class "Default")
      (node (ref "U7") (pin "T6") (pinfunction "PJ2_T6") (pintype "passive"))
    )
    (net (code "60") (name "/LCD_R4") (class "Default")
      (node (ref "U7") (pin "U6") (pinfunction "PJ3_U6") (pintype "passive"))
    )
    (net (code "61") (name "/LCD_R5") (class "Default")
      (node (ref "U7") (pin "U7") (pinfunction "PJ4_U7") (pintype "passive"))
    )
    (net (code "62") (name "/LCD_R6") (class "Default")
      (node (ref "U7") (pin "R12") (pinfunction "PJ5_R12") (pintype "passive"))
    )
    (net (code "63") (name "/LCD_R7") (class "Default")
      (node (ref "U7") (pin "N15") (pinfunction "PJ6_N15") (pintype "passive"))
    )
    (net (code "65") (name "/PA0") (class "Default")
      (node (ref "U7") (pin "N5") (pinfunction "PA0_N5") (pintype "passive"))
    )
    (net (code "66") (name "/PA0_C") (class "Default")
      (node (ref "SB43") (pin "1") (pinfunction "1_1") (pintype "passive"))
      (node (ref "U7") (pin "T1") (pinfunction "PA0_C_T1") (pintype "passive"))
    )
    (net (code "67") (name "/PA1") (class "Default")
      (node (ref "U7") (pin "N4") (pinfunction "PA1_N4") (pintype "passive"))
    )
    (net (code "68") (name "/PA1_C") (class "Default")
      (node (ref "U7") (pin "T2") (pinfunction "PA1_C_T2") (pintype "passive"))
    )
    (net (code "69") (name "/PA2") (class "Default")
      (node (ref "U7") (pin "N3") (pinfunction "PA2_N3") (pintype "passive"))
    )
    (net (code "70") (name "/PA3") (class "Default")
      (node (ref "U7") (pin "U2") (pinfunction "PA3_U2") (pintype "passive"))
    )
    (net (code "71") (name "/PA4") (class "Default")
      (node (ref "U7") (pin "U3") (pinfunction "PA4_U3") (pintype "passive"))
    )
    (net (code "72") (name "/PA5") (class "Default")
      (node (ref "U7") (pin "T3") (pinfunction "PA5_T3") (pintype "passive"))
    )
    (net (code "73") (name "/PA6") (class "Default")
      (node (ref "U7") (pin "R3") (pinfunction "PA6_R3") (pintype "passive"))
    )
    (net (code "74") (name "/PA7") (class "Default")
      (node (ref "U7") (pin "R5") (pinfunction "PA7_R5") (pintype "passive"))
    )
    (net (code "75") (name "/PA8") (class "Default")
      (node (ref "U7") (pin "E15") (pinfunction "PA8_E15") (pintype "passive"))
    )
    (net (code "76") (name "/PA9") (class "Default")
      (node (ref "R255") (pin "2") (pinfunction "2_2") (pintype "passive"))
      (node (ref "U7") (pin "D15") (pinfunction "PA9_D15") (pintype "passive"))
    )
    (net (code "77") (name "/PA10") (class "Default")
      (node (ref "U7") (pin "D14") (pinfunction "PA10_D14") (pintype "passive"))
    )
    (net (code "78") (name "/PA11") (class "Default")
      (node (ref "SB50") (pin "2") (pinfunction "2_2") (pintype "passive"))
      (node (ref "SB59") (pin "2") (pinfunction "2_2") (pintype "passive"))
      (node (ref "U7") (pin "E17") (pinfunction "PA11_E17") (pintype "passive"))
    )
    (net (code "79") (name "/PA12") (class "Default")
      (node (ref "JP2") (pin "1") (pinfunction "COMMON_1") (pintype "passive"))
      (node (ref "SB60") (pin "2") (pinfunction "2_2") (pintype "passive"))
      (node (ref "U7") (pin "E16") (pinfunction "PA12_E16") (pintype "passive"))
    )
    (net (code "80") (name "/PA13") (class "Default")
      (node (ref "U7") (pin "C15") (pinfunction "PA13_C15") (pintype "passive"))
    )
    (net (code "81") (name "/PA14") (class "Default")
      (node (ref "U7") (pin "B14") (pinfunction "PA14_B14") (pintype "passive"))
    )
    (net (code "82") (name "/PA15") (class "Default")
      (node (ref "U7") (pin "A14") (pinfunction "PA15_A14") (pintype "passive"))
    )
    (net (code "84") (name "/PB0") (class "Default")
      (node (ref "U7") (pin "U5") (pinfunction "PB0_U5") (pintype "passive"))
    )
    (net (code "85") (name "/PB1") (class "Default")
      (node (ref "U7") (pin "T5") (pinfunction "PB1_T5") (pintype "passive"))
    )
    (net (code "86") (name "/PB2") (class "Default")
      (node (ref "R34") (pin "2") (pinfunction "2_2") (pintype "passive"))
    )
    (net (code "87") (name "/PB3") (class "Default")
      (node (ref "U7") (pin "C6") (pinfunction "PB3_C6") (pintype "passive"))
    )
    (net (code "88") (name "/PB4") (class "Default")
      (node (ref "U7") (pin "B7") (pinfunction "PB4_B7") (pintype "passive"))
    )
    (net (code "89") (name "/PB5") (class "Default")
      (node (ref "U7") (pin "A5") (pinfunction "PB5_A5") (pintype "passive"))
    )
    (net (code "90") (name "/PB6") (class "Default")
      (node (ref "U7") (pin "B5") (pinfunction "PB6_B5") (pintype "passive"))
    )
    (net (code "91") (name "/PB7") (class "Default")
      (node (ref "U7") (pin "C5") (pinfunction "PB7_C5") (pintype "passive"))
    )
    (net (code "92") (name "/PB8") (class "Default")
      (node (ref "U7") (pin "D5") (pinfunction "PB8_D5") (pintype "passive"))
    )
    (net (code "93") (name "/PB9") (class "Default")
      (node (ref "U7") (pin "D4") (pinfunction "PB9_D4") (pintype "passive"))
    )
    (net (code "94") (name "/PB10") (class "Default")
      (node (ref "U7") (pin "P11") (pinfunction "PB10_P11") (pintype "passive"))
    )
    (net (code "95") (name "/PB11") (class "Default")
      (node (ref "U7") (pin "P12") (pinfunction "PB11_P12") (pintype "passive"))
    )
    (net (code "96") (name "/PB12") (class "Default")
      (node (ref "SB48") (pin "2") (pinfunction "2_2") (pintype "passive"))
      (node (ref "U7") (pin "T14") (pinfunction "PB12_T14") (pintype "passive"))
    )
    (net (code "97") (name "/PB13") (class "Default")
      (node (ref "R254") (pin "2") (pinfunction "2_2") (pintype "passive"))
      (node (ref "U7") (pin "U14") (pinfunction "PB13_U14") (pintype "passive"))
    )
    (net (code "98") (name "/PB14") (class "Default")
      (node (ref "SB46") (pin "2") (pinfunction "2_2") (pintype "passive"))
      (node (ref "SB47") (pin "2") (pinfunction "2_2") (pintype "passive"))
      (node (ref "U7") (pin "U15") (pinfunction "PB14_U15") (pintype "passive"))
    )
    (net (code "99") (name "/PB15") (class "Default")
      (node (ref "SB49") (pin "2") (pinfunction "2_2") (pintype "passive"))
      (node (ref "SB51") (pin "2") (pinfunction "2_2") (pintype "passive"))
      (node (ref "U7") (pin "T15") (pinfunction "PB15_T15") (pintype "passive"))
    )
    (net (code "101") (name "/PC0") (class "Default")
      (node (ref "U7") (pin "L2") (pinfunction "PC0_L2") (pintype "passive"))
    )
    (net (code "102") (name "/PC1") (class "Default")
      (node (ref "SB38") (pin "2") (pinfunction "2_2") (pintype "passive"))
      (node (ref "U7") (pin "M2") (pinfunction "PC1_M2") (pintype "passive"))
    )
    (net (code "103") (name "/PC2") (class "Default")
      (node (ref "U7") (pin "M3") (pinfunction "PC2_M3") (pintype "passive"))
    )
    (net (code "104") (name "/PC2_C") (class "Default")
      (node (ref "U7") (pin "R1") (pinfunction "PC2_C_R1") (pintype "passive"))
    )
    (net (code "105") (name "/PC3") (class "Default")
      (node (ref "U7") (pin "M4") (pinfunction "PC3_M4") (pintype "passive"))
    )
    (net (code "106") (name "/PC3_C") (class "Default")
      (node (ref "U7") (pin "R2") (pinfunction "PC3_C_R2") (pintype "passive"))
    )
    (net (code "107") (name "/PC4") (class "Default")
      (node (ref "U7") (pin "T4") (pinfunction "PC4_T4") (pintype "passive"))
    )
    (net (code "108") (name "/PC5") (class "Default")
      (node (ref "U7") (pin "U4") (pinfunction "PC5_U4") (pintype "passive"))
    )
    (net (code "109") (name "/PC6") (class "Default")
      (node (ref "SB58") (pin "1") (pinfunction "1_1") (pintype "passive"))
      (node (ref "U7") (pin "F14") (pinfunction "PC6_F14") (pintype "passive"))
    )
    (net (code "110") (name "/PC7") (class "Default")
      (node (ref "U7") (pin "F13") (pinfunction "PC7_F13") (pintype "passive"))
    )
    (net (code "111") (name "/PC8") (class "Default")
      (node (ref "U7") (pin "E13") (pinfunction "PC8_E13") (pintype "passive"))
    )
    (net (code "112") (name "/PC9") (class "Default")
      (node (ref "U7") (pin "E14") (pinfunction "PC9_E14") (pintype "passive"))
    )
    (net (code "113") (name "/PC10") (class "Default")
      (node (ref "U7") (pin "A13") (pinfunction "PC10_A13") (pintype "passive"))
    )
    (net (code "114") (name "/PC11") (class "Default")
      (node (ref "SB45") (pin "2") (pinfunction "2_2") (pintype "passive"))
      (node (ref "U7") (pin "B13") (pinfunction "PC11_B13") (pintype "passive"))
    )
    (net (code "115") (name "/PC12") (class "Default")
      (node (ref "U7") (pin "C12") (pinfunction "PC12_C12") (pintype "passive"))
    )
    (net (code "116") (name "/PC13") (class "Default")
      (node (ref "U7") (pin "E3") (pinfunction "PC13_E3") (pintype "passive"))
    )
    (net (code "117") (name "/PC14") (class "Default")
      (node (ref "R18") (pin "1") (pinfunction "1_1") (pintype "passive"))
      (node (ref "U7") (pin "C2") (pinfunction "PC14-OSC32_IN_C2") (pintype "passive"))
    )
    (net (code "118") (name "/PC15") (class "Default")
      (node (ref "R17") (pin "1") (pinfunction "1_1") (pintype "passive"))
      (node (ref "U7") (pin "C1") (pinfunction "PC15-OSC32_OUT_C1") (pintype "passive"))
    )
    (net (code "120") (name "/PD0") (class "Default")
      (node (ref "R265") (pin "1") (pinfunction "1_1") (pintype "passive"))
    )
    (net (code "121") (name "/PD1") (class "Default")
      (node (ref "R262") (pin "1") (pinfunction "1_1") (pintype "passive"))
    )
    (net (code "122") (name "/PD2") (class "Default")
      (node (ref "U7") (pin "D12") (pinfunction "PD2_D12") (pintype "passive"))
    )
    (net (code "123") (name "/PD3") (class "Default")
      (node (ref "U7") (pin "B12") (pinfunction "PD3_B12") (pintype "passive"))
    )
    (net (code "124") (name "/PD4") (class "Default")
      (node (ref "U7") (pin "A12") (pinfunction "PD4_A12") (pintype "passive"))
    )
    (net (code "125") (name "/PD5") (class "Default")
      (node (ref "U7") (pin "A11") (pinfunction "PD5_A11") (pintype "passive"))
    )
    (net (code "126") (name "/PD6") (class "Default")
      (node (ref "U7") (pin "B11") (pinfunction "PD6_B11") (pintype "passive"))
    )
    (net (code "127") (name "/PD7") (class "Default")
      (node (ref "U7") (pin "C11") (pinfunction "PD7_C11") (pintype "passive"))
    )
    (net (code "128") (name "/PD8") (class "Default")
      (node (ref "R73") (pin "1") (pinfunction "1_1") (pintype "passive"))
    )
    (net (code "129") (name "/PD9") (class "Default")
      (node (ref "R76") (pin "1") (pinfunction "1_1") (pintype "passive"))
    )
    (net (code "130") (name "/PD10") (class "Default")
      (node (ref "R75") (pin "1") (pinfunction "1_1") (pintype "passive"))
    )
    (net (code "131") (name "/PD11") (class "Default")
      (node (ref "R275") (pin "2") (pinfunction "2_2") (pintype "passive"))
    )
    (net (code "132") (name "/PD12") (class "Default")
      (node (ref "R274") (pin "1") (pinfunction "1_1") (pintype "passive"))
    )
    (net (code "133") (name "/PD13") (class "Default")
      (node (ref "R271") (pin "1") (pinfunction "1_1") (pintype "passive"))
    )
    (net (code "134") (name "/PD14") (class "Default")
      (node (ref "R77") (pin "1") (pinfunction "1_1") (pintype "passive"))
    )
    (net (code "135") (name "/PD15") (class "Default")
      (node (ref "R269") (pin "1") (pinfunction "1_1") (pintype "passive"))
    )
    (net (code "136") (name "/PDM1_CLK1") (class "Default")
      (node (ref "SB11") (pin "1") (pinfunction "1_1") (pintype "passive"))
    )
    (net (code "138") (name "/PE0") (class "Default")
      (node (ref "U7") (pin "C4") (pinfunction "PE0_C4") (pintype "passive"))
    )
    (net (code "139") (name "/PE1") (class "Default")
      (node (ref "U7") (pin "B4") (pinfunction "PE1_B4") (pintype "passive"))
    )
    (net (code "140") (name "/PE2") (class "Default")
      (node (ref "R234") (pin "1") (pinfunction "1_1") (pintype "passive"))
      (node (ref "R241") (pin "1") (pinfunction "1_1") (pintype "passive"))
    )
    (net (code "141") (name "/PE3") (class "Default")
      (node (ref "R236") (pin "1") (pinfunction "1_1") (pintype "passive"))
      (node (ref "R238") (pin "1") (pinfunction "1_1") (pintype "passive"))
    )
    (net (code "142") (name "/PE4") (class "Default")
      (node (ref "R231") (pin "1") (pinfunction "1_1") (pintype "passive"))
      (node (ref "R233") (pin "1") (pinfunction "1_1") (pintype "passive"))
    )
    (net (code "143") (name "/PE5") (class "Default")
      (node (ref "R217") (pin "1") (pinfunction "1_1") (pintype "passive"))
      (node (ref "R218") (pin "1") (pinfunction "1_1") (pintype "passive"))
    )
    (net (code "144") (name "/PE6") (class "Default")
      (node (ref "R227") (pin "1") (pinfunction "1_1") (pintype "passive"))
      (node (ref "R230") (pin "1") (pinfunction "1_1") (pintype "passive"))
    )
    (net (code "145") (name "/PE7") (class "Default")
      (node (ref "R54") (pin "1") (pinfunction "1_1") (pintype "passive"))
    )
    (net (code "146") (name "/PE8") (class "Default")
      (node (ref "R67") (pin "1") (pinfunction "1_1") (pintype "passive"))
    )
    (net (code "147") (name "/PE9") (class "Default")
      (node (ref "R66") (pin "1") (pinfunction "1_1") (pintype "passive"))
    )
    (net (code "148") (name "/PE10") (class "Default")
      (node (ref "R280") (pin "1") (pinfunction "1_1") (pintype "passive"))
    )
    (net (code "149") (name "/PE11") (class "Default")
      (node (ref "R68") (pin "1") (pinfunction "1_1") (pintype "passive"))
    )
    (net (code "150") (name "/PE12") (class "Default")
      (node (ref "R278") (pin "1") (pinfunction "1_1") (pintype "passive"))
    )
    (net (code "151") (name "/PE13") (class "Default")
      (node (ref "R70") (pin "1") (pinfunction "1_1") (pintype "passive"))
    )
    (net (code "152") (name "/PE14") (class "Default")
      (node (ref "R277") (pin "1") (pinfunction "1_1") (pintype "passive"))
    )
    (net (code "153") (name "/PE15") (class "Default")
      (node (ref "R69") (pin "1") (pinfunction "1_1") (pintype "passive"))
    )
    (net (code "155") (name "/PF0") (class "Default")
      (node (ref "R224") (pin "1") (pinfunction "1_1") (pintype "passive"))
    )
    (net (code "156") (name "/PF1") (class "Default")
      (node (ref "R226") (pin "1") (pinfunction "1_1") (pintype "passive"))
    )
    (net (code "157") (name "/PF2") (class "Default")
      (node (ref "R222") (pin "1") (pinfunction "1_1") (pintype "passive"))
    )
    (net (code "158") (name "/PF3") (class "Default")
      (node (ref "R223") (pin "1") (pinfunction "1_1") (pintype "passive"))
    )
    (net (code "159") (name "/PF4") (class "Default")
      (node (ref "R221") (pin "1") (pinfunction "1_1") (pintype "passive"))
    )
    (net (code "160") (name "/PF5") (class "Default")
      (node (ref "R219") (pin "1") (pinfunction "1_1") (pintype "passive"))
    )
    (net (code "161") (name "/PF6") (class "Default")
      (node (ref "R14") (pin "1") (pinfunction "1_1") (pintype "passive"))
    )
    (net (code "162") (name "/PF7") (class "Default")
      (node (ref "R13") (pin "1") (pinfunction "1_1") (pintype "passive"))
    )
    (net (code "163") (name "/PF8") (class "Default")
      (node (ref "R232") (pin "1") (pinfunction "1_1") (pintype "passive"))
    )
    (net (code "164") (name "/PF9") (class "Default")
      (node (ref "R239") (pin "1") (pinfunction "1_1") (pintype "passive"))
    )
    (net (code "165") (name "/PF10") (class "Default")
      (node (ref "U7") (pin "L3") (pinfunction "PF10_L3") (pintype "passive"))
    )
    (net (code "166") (name "/PF11") (class "Default")
      (node (ref "R252") (pin "1") (pinfunction "1_1") (pintype "passive"))
    )
    (net (code "167") (name "/PF12") (class "Default")
      (node (ref "R250") (pin "1") (pinfunction "1_1") (pintype "passive"))
    )
    (net (code "168") (name "/PF13") (class "Default")
      (node (ref "R251") (pin "1") (pinfunction "1_1") (pintype "passive"))
    )
    (net (code "169") (name "/PF14") (class "Default")
      (node (ref "R53") (pin "1") (pinfunction "1_1") (pintype "passive"))
    )
    (net (code "170") (name "/PF15") (class "Default")
      (node (ref "R279") (pin "1") (pinfunction "1_1") (pintype "passive"))
    )
    (net (code "172") (name "/PG6") (class "Default")
      (node (ref "R259") (pin "2") (pinfunction "2_2") (pintype "passive"))
    )
    (net (code "173") (name "/PG7") (class "Default")
      (node (ref "SB56") (pin "2") (pinfunction "2_2") (pintype "passive"))
      (node (ref "U7") (pin "F16") (pinfunction "PG7_F16") (pintype "passive"))
    )
    (net (code "174") (name "/PG8") (class "Default")
      (node (ref "R268") (pin "1") (pinfunction "1_1") (pintype "passive"))
    )
    (net (code "175") (name "/PG9") (class "Default")
      (node (ref "R244") (pin "2") (pinfunction "2_2") (pintype "passive"))
    )
    (net (code "176") (name "/PG10") (class "Default")
      (node (ref "U7") (pin "A9") (pinfunction "PG10_A9") (pintype "passive"))
    )
    (net (code "177") (name "/PG11") (class "Default")
      (node (ref "R49") (pin "1") (pinfunction "1_1") (pintype "passive"))
    )
    (net (code "178") (name "/PG12") (class "Default")
      (node (ref "R48") (pin "1") (pinfunction "1_1") (pintype "passive"))
    )
    (net (code "179") (name "/PG13") (class "Default")
      (node (ref "R37") (pin "1") (pinfunction "1_1") (pintype "passive"))
    )
    (net (code "180") (name "/PG14") (class "Default")
      (node (ref "R29") (pin "2") (pinfunction "2_2") (pintype "passive"))
    )
    (net (code "181") (name "/PG15") (class "Default")
      (node (ref "R245") (pin "1") (pinfunction "1_1") (pintype "passive"))
    )
    (net (code "183") (name "/PH0") (class "Default")
      (node (ref "R15") (pin "2") (pinfunction "2_2") (pintype "passive"))
      (node (ref "U7") (pin "J2") (pinfunction "PH0-OSCIN_J2") (pintype "passive"))
    )
    (net (code "184") (name "/PH1") (class "Default")
      (node (ref "R16") (pin "2") (pinfunction "2_2") (pintype "passive"))
      (node (ref "U7") (pin "J1") (pinfunction "PH1-OSCOUT_J1") (pintype "passive"))
    )
    (net (code "185") (name "/PH2") (class "Default")
      (node (ref "R228") (pin "2") (pinfunction "2_2") (pintype "passive"))
    )
    (net (code "186") (name "/PH3") (class "Default")
      (node (ref "R235") (pin "2") (pinfunction "2_2") (pintype "passive"))
    )
    (net (code "187") (name "/PH4") (class "Default")
      (node (ref "U7") (pin "P3") (pinfunction "PH4_P3") (pintype "passive"))
    )
    (net (code "188") (name "/PH5") (class "Default")
      (node (ref "R248") (pin "2") (pinfunction "2_2") (pintype "passive"))
    )
    (net (code "189") (name "/PH6") (class "Default")
      (node (ref "R58") (pin "2") (pinfunction "2_2") (pintype "passive"))
    )
    (net (code "190") (name "/PH7") (class "Default")
      (node (ref "U7") (pin "U13") (pinfunction "PH7_U13") (pintype "passive"))
    )
    (net (code "192") (name "/PI4") (class "Default")
      (node (ref "U7") (pin "A4") (pinfunction "PI4_A4") (pintype "passive"))
    )
    (net (code "193") (name "/PI5") (class "Default")
      (node (ref "U7") (pin "A3") (pinfunction "PI5_A3") (pintype "passive"))
    )
    (net (code "194") (name "/PI8") (class "Default")
      (node (ref "U7") (pin "E4") (pinfunction "PI8_E4") (pintype "passive"))
    )
    (net (code "195") (name "/PI11") (class "Default")
      (node (ref "U7") (pin "F4") (pinfunction "PI11_F4") (pintype "passive"))
    )
    (net (code "196") (name "/PI12") (class "Default")
      (node (ref "U7") (pin "H1") (pinfunction "PI12_H1") (pintype "passive"))
    )
    (net (code "197") (name "/PI13") (class "Default")
      (node (ref "U7") (pin "H2") (pinfunction "PI13_H2") (pintype "passive"))
    )
    (net (code "198") (name "/PI14") (class "Default")
      (node (ref "R220") (pin "1") (pinfunction "1_1") (pintype "passive"))
    )
    (net (code "201") (name "/PK7") (class "Default")
      (node (ref "U7") (pin "D7") (pinfunction "PK7_D7") (pintype "passive"))
    )
    (net (code "203") (name "/Potentiometer") (class "Default")
      (node (ref "SB43") (pin "2") (pinfunction "2_2") (pintype "passive"))
    )
    (net (code "204") (name "/QSPI_BK2_NCS") (class "Default")
      (node (ref "SB45") (pin "1") (pinfunction "1_1") (pintype "passive"))
    )
    (net (code "205") (name "/RESET#") (class "Default")
      (node (ref "B1") (pin "2") (pinfunction "B0_2") (pintype "passive"))
      (node (ref "B1") (pin "3") (pinfunction "B1_3") (pintype "passive"))
      (node (ref "C94") (pin "2") (pinfunction "2_2") (pintype "passive"))
      (node (ref "D1") (pin "1") (pinfunction "A_1") (pintype "passive"))
      (node (ref "U7") (pin "K1") (pinfunction "NRST_K1") (pintype "passive"))
    )
    (net (code "206") (name "/SAI1_FSA") (class "Default")
      (node (ref "SB5") (pin "1") (pinfunction "1_1") (pintype "passive"))
    )
    (net (code "207") (name "/SAI1_MCLKA") (class "Default")
      (node (ref "SB56") (pin "1") (pinfunction "1_1") (pintype "passive"))
      (node (ref "SB57") (pin "1") (pinfunction "1_1") (pintype "passive"))
    )
    (net (code "208") (name "/SAI1_SCKA") (class "Default")
      (node (ref "SB42") (pin "1") (pinfunction "1_1") (pintype "passive"))
    )
    (net (code "209") (name "/SAI1_SDA") (class "Default")
      (node (ref "SB2") (pin "1") (pinfunction "1_1") (pintype "passive"))
    )
    (net (code "210") (name "/SAI1_SDB") (class "Default")
      (node (ref "SB8") (pin "1") (pinfunction "1_1") (pintype "passive"))
    )
    (net (code "211") (name "/SDIO1_D0DIR") (class "Default")
      (node (ref "SB58") (pin "2") (pinfunction "2_2") (pintype "passive"))
    )
    (net (code "212") (name "/TRACE_CK") (class "Default")
      (node (ref "SB15") (pin "1") (pinfunction "1_1") (pintype "passive"))
    )
    (net (code "213") (name "/TRACE_D0") (class "Default")
      (node (ref "SB9") (pin "1") (pinfunction "1_1") (pintype "passive"))
    )
    (net (code "214") (name "/TRACE_D1") (class "Default")
      (node (ref "SB7") (pin "1") (pinfunction "1_1") (pintype "passive"))
    )
    (net (code "215") (name "/TRACE_D2") (class "Default")
      (node (ref "SB41") (pin "1") (pinfunction "1_1") (pintype "passive"))
    )
    (net (code "216") (name "/TRACE_D3") (class "Default")
      (node (ref "SB3") (pin "1") (pinfunction "1_1") (pintype "passive"))
    )
    (net (code "218") (name "/USART1_RX") (class "Default")
      (node (ref "SB51") (pin "1") (pinfunction "1_1") (pintype "passive"))
    )
    (net (code "219") (name "/USART1_TX") (class "Default")
      (node (ref "SB46") (pin "1") (pinfunction "1_1") (pintype "passive"))
    )
    (net (code "220") (name "/USB_FS1_DM") (class "Default")
      (node (ref "SB59") (pin "1") (pinfunction "1_1") (pintype "passive"))
    )
    (net (code "221") (name "/USB_FS1_DP") (class "Default")
      (node (ref "SB60") (pin "1") (pinfunction "1_1") (pintype "passive"))
    )
    (net (code "222") (name "/USB_FS2_DM") (class "Default")
      (node (ref "SB47") (pin "1") (pinfunction "1_1") (pintype "passive"))
    )
    (net (code "223") (name "/USB_FS2_DP") (class "Default")
      (node (ref "SB49") (pin "1") (pinfunction "1_1") (pintype "passive"))
    )
    (net (code "224") (name "/USB_FS2_ID") (class "Default")
      (node (ref "SB48") (pin "1") (pinfunction "1_1") (pintype "passive"))
    )
    (net (code "225") (name "GND") (class "Default")
      (node (ref "B1") (pin "1") (pinfunction "A0_1") (pintype "passive"))
      (node (ref "B1") (pin "4") (pinfunction "A1_4") (pintype "passive"))
      (node (ref "C10") (pin "2") (pinfunction "2_2") (pintype "passive"))
      (node (ref "C11") (pin "2") (pinfunction "2_2") (pintype "passive"))
      (node (ref "C8") (pin "2") (pinfunction "2_2") (pintype "passive"))
      (node (ref "C9") (pin "2") (pinfunction "2_2") (pintype "passive"))
      (node (ref "C94") (pin "1") (pinfunction "1_1") (pintype "passive"))
      (node (ref "R218") (pin "2") (pinfunction "2_2") (pintype "passive"))
      (node (ref "R227") (pin "2") (pinfunction "2_2") (pintype "passive"))
      (node (ref "R233") (pin "2") (pinfunction "2_2") (pintype "passive"))
      (node (ref "R238") (pin "2") (pinfunction "2_2") (pintype "passive"))
      (node (ref "R241") (pin "2") (pinfunction "2_2") (pintype "passive"))
      (node (ref "R249") (pin "1") (pinfunction "1_1") (pintype "passive"))
      (node (ref "SW1") (pin "3") (pintype "passive"))
      (node (ref "X1") (pin "2") (pinfunction "2_2") (pintype "passive"))
      (node (ref "X1") (pin "4") (pinfunction "4_4") (pintype "passive"))
    )
    (net (code "226") (name "Net-(C8-Pad1)") (class "Default")
      (node (ref "C8") (pin "1") (pinfunction "1_1") (pintype "passive"))
      (node (ref "R15") (pin "1") (pinfunction "1_1") (pintype "passive"))
      (node (ref "X1") (pin "3") (pinfunction "3_3") (pintype "passive"))
    )
    (net (code "227") (name "Net-(C9-Pad1)") (class "Default")
      (node (ref "C9") (pin "1") (pinfunction "1_1") (pintype "passive"))
      (node (ref "R16") (pin "1") (pinfunction "1_1") (pintype "passive"))
      (node (ref "X1") (pin "1") (pinfunction "1_1") (pintype "passive"))
    )
    (net (code "228") (name "Net-(C10-Pad1)") (class "Default")
      (node (ref "C10") (pin "1") (pinfunction "1_1") (pintype "passive"))
      (node (ref "R17") (pin "2") (pinfunction "2_2") (pintype "passive"))
      (node (ref "X2") (pin "1") (pinfunction "1_1") (pintype "passive"))
    )
    (net (code "229") (name "Net-(C11-Pad1)") (class "Default")
      (node (ref "C11") (pin "1") (pinfunction "1_1") (pintype "passive"))
      (node (ref "R18") (pin "2") (pinfunction "2_2") (pintype "passive"))
      (node (ref "X2") (pin "2") (pinfunction "2_2") (pintype "passive"))
    )
    (net (code "230") (name "Net-(D1-K)") (class "Default")
      (node (ref "D1") (pin "2") (pinfunction "K_2") (pintype "passive"))
      (node (ref "JP6") (pin "1") (pinfunction "COMMON_1") (pintype "passive"))
    )
    (net (code "231") (name "Net-(D3-K)") (class "Default")
      (node (ref "D3") (pin "2") (pinfunction "K_2") (pintype "passive"))
      (node (ref "JP3") (pin "1") (pinfunction "COMMON_1") (pintype "passive"))
    )
    (net (code "232") (name "Net-(R3-Pad2)") (class "Default")
      (node (ref "R3") (pin "2") (pinfunction "2_2") (pintype "passive"))
      (node (ref "SW1") (pin "2") (pintype "passive"))
    )
    (net (code "233") (name "Net-(U7A-PB2)") (class "Default")
      (node (ref "R34") (pin "1") (pinfunction "1_1") (pintype "passive"))
      (node (ref "U7") (pin "R6") (pinfunction "PB2_R6") (pintype "passive"))
    )
    (net (code "234") (name "Net-(U7A-PD0)") (class "Default")
      (node (ref "R265") (pin "2") (pinfunction "2_2") (pintype "passive"))
      (node (ref "U7") (pin "D13") (pinfunction "PD0_D13") (pintype "passive"))
    )
    (net (code "235") (name "Net-(U7A-PD1)") (class "Default")
      (node (ref "R262") (pin "2") (pinfunction "2_2") (pintype "passive"))
      (node (ref "U7") (pin "E12") (pinfunction "PD1_E12") (pintype "passive"))
    )
    (net (code "236") (name "Net-(U7A-PD8)") (class "Default")
      (node (ref "R73") (pin "2") (pinfunction "2_2") (pintype "passive"))
      (node (ref "U7") (pin "U16") (pinfunction "PD8_U16") (pintype "passive"))
    )
    (net (code "237") (name "Net-(U7A-PD9)") (class "Default")
      (node (ref "R76") (pin "2") (pinfunction "2_2") (pintype "passive"))
      (node (ref "U7") (pin "T17") (pinfunction "PD9_T17") (pintype "passive"))
    )
    (net (code "238") (name "Net-(U7A-PD10)") (class "Default")
      (node (ref "R75") (pin "2") (pinfunction "2_2") (pintype "passive"))
      (node (ref "U7") (pin "T16") (pinfunction "PD10_T16") (pintype "passive"))
    )
    (net (code "239") (name "Net-(U7A-PD11)") (class "Default")
      (node (ref "R275") (pin "1") (pinfunction "1_1") (pintype "passive"))
      (node (ref "U7") (pin "R15") (pinfunction "PD11_R15") (pintype "passive"))
    )
    (net (code "240") (name "Net-(U7A-PD12)") (class "Default")
      (node (ref "R274") (pin "2") (pinfunction "2_2") (pintype "passive"))
      (node (ref "U7") (pin "R16") (pinfunction "PD12_R16") (pintype "passive"))
    )
    (net (code "241") (name "Net-(U7A-PD13)") (class "Default")
      (node (ref "R271") (pin "2") (pinfunction "2_2") (pintype "passive"))
      (node (ref "U7") (pin "R17") (pinfunction "PD13_R17") (pintype "passive"))
    )
    (net (code "242") (name "Net-(U7A-PD14)") (class "Default")
      (node (ref "R77") (pin "2") (pinfunction "2_2") (pintype "passive"))
      (node (ref "U7") (pin "P16") (pinfunction "PD14_P16") (pintype "passive"))
    )
    (net (code "243") (name "Net-(U7A-PD15)") (class "Default")
      (node (ref "R269") (pin "2") (pinfunction "2_2") (pintype "passive"))
      (node (ref "U7") (pin "P15") (pinfunction "PD15_P15") (pintype "passive"))
    )
    (net (code "244") (name "Net-(U7A-PE2)") (class "Default")
      (node (ref "R234") (pin "2") (pinfunction "2_2") (pintype "passive"))
      (node (ref "SB11") (pin "2") (pinfunction "2_2") (pintype "passive"))
      (node (ref "SB15") (pin "2") (pinfunction "2_2") (pintype "passive"))
      (node (ref "SB57") (pin "2") (pinfunction "2_2") (pintype "passive"))
      (node (ref "U7") (pin "C3") (pinfunction "PE2_C3") (pintype "passive"))
    )
    (net (code "245") (name "Net-(U7A-PE3)") (class "Default")
      (node (ref "R236") (pin "2") (pinfunction "2_2") (pintype "passive"))
      (node (ref "SB8") (pin "2") (pinfunction "2_2") (pintype "passive"))
      (node (ref "SB9") (pin "2") (pinfunction "2_2") (pintype "passive"))
      (node (ref "U7") (pin "D3") (pinfunction "PE3_D3") (pintype "passive"))
    )
    (net (code "246") (name "Net-(U7A-PE4)") (class "Default")
      (node (ref "R231") (pin "2") (pinfunction "2_2") (pintype "passive"))
      (node (ref "SB5") (pin "2") (pinfunction "2_2") (pintype "passive"))
      (node (ref "SB7") (pin "2") (pinfunction "2_2") (pintype "passive"))
      (node (ref "U7") (pin "D2") (pinfunction "PE4_D2") (pintype "passive"))
    )
    (net (code "247") (name "Net-(U7A-PE5)") (class "Default")
      (node (ref "R217") (pin "2") (pinfunction "2_2") (pintype "passive"))
      (node (ref "SB41") (pin "2") (pinfunction "2_2") (pintype "passive"))
      (node (ref "SB42") (pin "2") (pinfunction "2_2") (pintype "passive"))
      (node (ref "U7") (pin "D1") (pinfunction "PE5_D1") (pintype "passive"))
    )
    (net (code "248") (name "Net-(U7A-PE6)") (class "Default")
      (node (ref "R230") (pin "2") (pinfunction "2_2") (pintype "passive"))
      (node (ref "SB2") (pin "2") (pinfunction "2_2") (pintype "passive"))
      (node (ref "SB3") (pin "2") (pinfunction "2_2") (pintype "passive"))
      (node (ref "U7") (pin "E5") (pinfunction "PE6_E5") (pintype "passive"))
    )
    (net (code "249") (name "Net-(U7A-PE7)") (class "Default")
      (node (ref "R54") (pin "2") (pinfunction "2_2") (pintype "passive"))
      (node (ref "U7") (pin "U9") (pinfunction "PE7_U9") (pintype "passive"))
    )
    (net (code "250") (name "Net-(U7A-PE8)") (class "Default")
      (node (ref "R67") (pin "2") (pinfunction "2_2") (pintype "passive"))
      (node (ref "U7") (pin "T9") (pinfunction "PE8_T9") (pintype "passive"))
    )
    (net (code "251") (name "Net-(U7A-PE9)") (class "Default")
      (node (ref "R66") (pin "2") (pinfunction "2_2") (pintype "passive"))
      (node (ref "U7") (pin "P9") (pinfunction "PE9_P9") (pintype "passive"))
    )
    (net (code "252") (name "Net-(U7A-PE10)") (class "Default")
      (node (ref "R280") (pin "2") (pinfunction "2_2") (pintype "passive"))
      (node (ref "U7") (pin "N9") (pinfunction "PE10_N9") (pintype "passive"))
    )
    (net (code "253") (name "Net-(U7A-PE11)") (class "Default")
      (node (ref "R68") (pin "2") (pinfunction "2_2") (pintype "passive"))
      (node (ref "U7") (pin "P10") (pinfunction "PE11_P10") (pintype "passive"))
    )
    (net (code "254") (name "Net-(U7A-PE12)") (class "Default")
      (node (ref "R278") (pin "2") (pinfunction "2_2") (pintype "passive"))
      (node (ref "U7") (pin "R10") (pinfunction "PE12_R10") (pintype "passive"))
    )
    (net (code "255") (name "Net-(U7A-PE13)") (class "Default")
      (node (ref "R70") (pin "2") (pinfunction "2_2") (pintype "passive"))
      (node (ref "U7") (pin "T10") (pinfunction "PE13_T10") (pintype "passive"))
    )
    (net (code "256") (name "Net-(U7A-PE14)") (class "Default")
      (node (ref "R277") (pin "2") (pinfunction "2_2") (pintype "passive"))
      (node (ref "U7") (pin "U10") (pinfunction "PE14_U10") (pintype "passive"))
    )
    (net (code "257") (name "Net-(U7A-PE15)") (class "Default")
      (node (ref "R69") (pin "2") (pinfunction "2_2") (pintype "passive"))
      (node (ref "U7") (pin "R11") (pinfunction "PE15_R11") (pintype "passive"))
    )
    (net (code "258") (name "Net-(U7A-PF0)") (class "Default")
      (node (ref "R224") (pin "2") (pinfunction "2_2") (pintype "passive"))
      (node (ref "U7") (pin "G4") (pinfunction "PF0_G4") (pintype "passive"))
    )
    (net (code "259") (name "Net-(U7A-PF1)") (class "Default")
      (node (ref "R226") (pin "2") (pinfunction "2_2") (pintype "passive"))
      (node (ref "U7") (pin "G3") (pinfunction "PF1_G3") (pintype "passive"))
    )
    (net (code "260") (name "Net-(U7A-PF2)") (class "Default")
      (node (ref "R222") (pin "2") (pinfunction "2_2") (pintype "passive"))
      (node (ref "U7") (pin "G1") (pinfunction "PF2_G1") (pintype "passive"))
    )
    (net (code "261") (name "Net-(U7A-PF3)") (class "Default")
      (node (ref "R223") (pin "2") (pinfunction "2_2") (pintype "passive"))
      (node (ref "U7") (pin "H4") (pinfunction "PF3_H4") (pintype "passive"))
    )
    (net (code "262") (name "Net-(U7A-PF4)") (class "Default")
      (node (ref "R221") (pin "2") (pinfunction "2_2") (pintype "passive"))
      (node (ref "U7") (pin "J5") (pinfunction "PF4_J5") (pintype "passive"))
    )
    (net (code "263") (name "Net-(U7A-PF5)") (class "Default")
      (node (ref "R219") (pin "2") (pinfunction "2_2") (pintype "passive"))
      (node (ref "U7") (pin "J4") (pinfunction "PF5_J4") (pintype "passive"))
    )
    (net (code "264") (name "Net-(U7A-PF6)") (class "Default")
      (node (ref "R14") (pin "2") (pinfunction "2_2") (pintype "passive"))
      (node (ref "U7") (pin "K2") (pinfunction "PF6_K2") (pintype "passive"))
    )
    (net (code "265") (name "Net-(U7A-PF7)") (class "Default")
      (node (ref "R13") (pin "2") (pinfunction "2_2") (pintype "passive"))
      (node (ref "U7") (pin "K3") (pinfunction "PF7_K3") (pintype "passive"))
    )
    (net (code "266") (name "Net-(U7A-PF8)") (class "Default")
      (node (ref "R232") (pin "2") (pinfunction "2_2") (pintype "passive"))
      (node (ref "U7") (pin "K4") (pinfunction "PF8_K4") (pintype "passive"))
    )
    (net (code "267") (name "Net-(U7A-PF9)") (class "Default")
      (node (ref "R239") (pin "2") (pinfunction "2_2") (pintype "passive"))
      (node (ref "U7") (pin "L4") (pinfunction "PF9_L4") (pintype "passive"))
    )
    (net (code "268") (name "Net-(U7A-PF11)") (class "Default")
      (node (ref "R252") (pin "2") (pinfunction "2_2") (pintype "passive"))
      (node (ref "U7") (pin "T7") (pinfunction "PF11_T7") (pintype "passive"))
    )
    (net (code "269") (name "Net-(U7A-PF12)") (class "Default")
      (node (ref "R250") (pin "2") (pinfunction "2_2") (pintype "passive"))
      (node (ref "U7") (pin "R7") (pinfunction "PF12_R7") (pintype "passive"))
    )
    (net (code "270") (name "Net-(U7A-PF13)") (class "Default")
      (node (ref "R251") (pin "2") (pinfunction "2_2") (pintype "passive"))
      (node (ref "U7") (pin "P7") (pinfunction "PF13_P7") (pintype "passive"))
    )
    (net (code "271") (name "Net-(U7A-PF14)") (class "Default")
      (node (ref "R53") (pin "2") (pinfunction "2_2") (pintype "passive"))
      (node (ref "U7") (pin "P8") (pinfunction "PF14_P8") (pintype "passive"))
    )
    (net (code "272") (name "Net-(U7A-PF15)") (class "Default")
      (node (ref "R279") (pin "2") (pinfunction "2_2") (pintype "passive"))
      (node (ref "U7") (pin "R9") (pinfunction "PF15_R9") (pintype "passive"))
    )
    (net (code "273") (name "Net-(U7B-PDR_ON)") (class "Default")
      (node (ref "R247") (pin "2") (pinfunction "2_2") (pintype "passive"))
      (node (ref "R249") (pin "2") (pinfunction "2_2") (pintype "passive"))
      (node (ref "U7") (pin "E7") (pinfunction "PDR_ON_E7") (pintype "passive"))
    )
    (net (code "274") (name "Net-(U7B-PG0)") (class "Default")
      (node (ref "R50") (pin "2") (pinfunction "2_2") (pintype "passive"))
      (node (ref "U7") (pin "T8") (pinfunction "PG0_T8") (pintype "passive"))
    )
    (net (code "275") (name "Net-(U7B-PG1)") (class "Default")
      (node (ref "R51") (pin "2") (pinfunction "2_2") (pintype "passive"))
      (node (ref "U7") (pin "U8") (pinfunction "PG1_U8") (pintype "passive"))
    )
    (net (code "276") (name "Net-(U7B-PG2)") (class "Default")
      (node (ref "R270") (pin "2") (pinfunction "2_2") (pintype "passive"))
      (node (ref "U7") (pin "H16") (pinfunction "PG2_H16") (pintype "passive"))
    )
    (net (code "277") (name "Net-(U7B-PG3)") (class "Default")
      (node (ref "R260") (pin "2") (pinfunction "2_2") (pintype "passive"))
      (node (ref "U7") (pin "H15") (pinfunction "PG3_H15") (pintype "passive"))
    )
    (net (code "278") (name "Net-(U7B-PG4)") (class "Default")
      (node (ref "R261") (pin "2") (pinfunction "2_2") (pintype "passive"))
      (node (ref "U7") (pin "H14") (pinfunction "PG4_H14") (pintype "passive"))
    )
    (net (code "279") (name "Net-(U7B-PG5)") (class "Default")
      (node (ref "R272") (pin "2") (pinfunction "2_2") (pintype "passive"))
      (node (ref "U7") (pin "G14") (pinfunction "PG5_G14") (pintype "passive"))
    )
    (net (code "280") (name "Net-(U7B-PG6)") (class "Default")
      (node (ref "R259") (pin "1") (pinfunction "1_1") (pintype "passive"))
      (node (ref "U7") (pin "G15") (pinfunction "PG6_G15") (pintype "passive"))
    )
    (net (code "281") (name "Net-(U7B-PG8)") (class "Default")
      (node (ref "R268") (pin "2") (pinfunction "2_2") (pintype "passive"))
      (node (ref "U7") (pin "F15") (pinfunction "PG8_F15") (pintype "passive"))
    )
    (net (code "282") (name "Net-(U7B-PG9)") (class "Default")
      (node (ref "R244") (pin "1") (pinfunction "1_1") (pintype "passive"))
      (node (ref "U7") (pin "A10") (pinfunction "PG9_A10") (pintype "passive"))
    )
    (net (code "283") (name "Net-(U7B-PG11)") (class "Default")
      (node (ref "R49") (pin "2") (pinfunction "2_2") (pintype "passive"))
      (node (ref "U7") (pin "B9") (pinfunction "PG11_B9") (pintype "passive"))
    )
    (net (code "284") (name "Net-(U7B-PG12)") (class "Default")
      (node (ref "R48") (pin "2") (pinfunction "2_2") (pintype "passive"))
      (node (ref "U7") (pin "C9") (pinfunction "PG12_C9") (pintype "passive"))
    )
    (net (code "285") (name "Net-(U7B-PG13)") (class "Default")
      (node (ref "R37") (pin "2") (pinfunction "2_2") (pintype "passive"))
      (node (ref "U7") (pin "D9") (pinfunction "PG13_D9") (pintype "passive"))
    )
    (net (code "286") (name "Net-(U7B-PG14)") (class "Default")
      (node (ref "R29") (pin "1") (pinfunction "1_1") (pintype "passive"))
      (node (ref "U7") (pin "D8") (pinfunction "PG14_D8") (pintype "passive"))
    )
    (net (code "287") (name "Net-(U7B-PG15)") (class "Default")
      (node (ref "R245") (pin "2") (pinfunction "2_2") (pintype "passive"))
      (node (ref "U7") (pin "D6") (pinfunction "PG15_D6") (pintype "passive"))
    )
    (net (code "288") (name "Net-(U7B-PH2)") (class "Default")
      (node (ref "R228") (pin "1") (pinfunction "1_1") (pintype "passive"))
      (node (ref "U7") (pin "N2") (pinfunction "PH2_N2") (pintype "passive"))
    )
    (net (code "289") (name "Net-(U7B-PH3)") (class "Default")
      (node (ref "R235") (pin "1") (pinfunction "1_1") (pintype "passive"))
      (node (ref "U7") (pin "P2") (pinfunction "PH3_P2") (pintype "passive"))
    )
    (net (code "290") (name "Net-(U7B-PH5)") (class "Default")
      (node (ref "R248") (pin "1") (pinfunction "1_1") (pintype "passive"))
      (node (ref "U7") (pin "P4") (pinfunction "PH5_P4") (pintype "passive"))
    )
    (net (code "291") (name "Net-(U7B-PH6)") (class "Default")
      (node (ref "R58") (pin "1") (pinfunction "1_1") (pintype "passive"))
      (node (ref "U7") (pin "T11") (pinfunction "PH6_T11") (pintype "passive"))
    )
    (net (code "292") (name "Net-(U7B-PH8)") (class "Default")
      (node (ref "R71") (pin "1") (pinfunction "1_1") (pintype "passive"))
      (node (ref "U7") (pin "T13") (pinfunction "PH8_T13") (pintype "passive"))
    )
    (net (code "293") (name "Net-(U7B-PH9)") (class "Default")
      (node (ref "R72") (pin "1") (pinfunction "1_1") (pintype "passive"))
      (node (ref "U7") (pin "R13") (pinfunction "PH9_R13") (pintype "passive"))
    )
    (net (code "294") (name "Net-(U7B-PH10)") (class "Default")
      (node (ref "R276") (pin "1") (pinfunction "1_1") (pintype "passive"))
      (node (ref "U7") (pin "P13") (pinfunction "PH10_P13") (pintype "passive"))
    )
    (net (code "295") (name "Net-(U7B-PH11)") (class "Default")
      (node (ref "R273") (pin "1") (pinfunction "1_1") (pintype "passive"))
      (node (ref "U7") (pin "P14") (pinfunction "PH11_P14") (pintype "passive"))
    )
    (net (code "296") (name "Net-(U7B-PH12)") (class "Default")
      (node (ref "R74") (pin "1") (pinfunction "1_1") (pintype "passive"))
      (node (ref "U7") (pin "R14") (pinfunction "PH12_R14") (pintype "passive"))
    )
    (net (code "297") (name "Net-(U7B-PH13)") (class "Default")
      (node (ref "R258") (pin "1") (pinfunction "1_1") (pintype "passive"))
      (node (ref "U7") (pin "D16") (pinfunction "PH13_D16") (pintype "passive"))
    )
    (net (code "298") (name "Net-(U7B-PH14)") (class "Default")
      (node (ref "R257") (pin "1") (pinfunction "1_1") (pintype "passive"))
      (node (ref "U7") (pin "B17") (pinfunction "PH14_B17") (pintype "passive"))
    )
    (net (code "299") (name "Net-(U7B-PH15)") (class "Default")
      (node (ref "R266") (pin "1") (pinfunction "1_1") (pintype "passive"))
      (node (ref "U7") (pin "B16") (pinfunction "PH15_B16") (pintype "passive"))
    )
    (net (code "300") (name "Net-(U7B-PI0)") (class "Default")
      (node (ref "R256") (pin "2") (pinfunction "2_2") (pintype "passive"))
      (node (ref "U7") (pin "A16") (pinfunction "PI0_A16") (pintype "passive"))
    )
    (net (code "301") (name "Net-(U7B-PI1)") (class "Default")
      (node (ref "R264") (pin "2") (pinfunction "2_2") (pintype "passive"))
      (node (ref "U7") (pin "A15") (pinfunction "PI1_A15") (pintype "passive"))
    )
    (net (code "302") (name "Net-(U7B-PI2)") (class "Default")
      (node (ref "R263") (pin "2") (pinfunction "2_2") (pintype "passive"))
      (node (ref "U7") (pin "B15") (pinfunction "PI2_B15") (pintype "passive"))
    )
    (net (code "303") (name "Net-(U7B-PI3)") (class "Default")
      (node (ref "R267") (pin "2") (pinfunction "2_2") (pintype "passive"))
      (node (ref "U7") (pin "C14") (pinfunction "PI3_C14") (pintype "passive"))
    )
    (net (code "304") (name "Net-(U7B-PI6)") (class "Default")
      (node (ref "R243") (pin "2") (pinfunction "2_2") (pintype "passive"))
      (node (ref "U7") (pin "A2") (pinfunction "PI6_A2") (pintype "passive"))
    )
    (net (code "305") (name "Net-(U7B-PI7)") (class "Default")
      (node (ref "R240") (pin "2") (pinfunction "2_2") (pintype "passive"))
      (node (ref "U7") (pin "B3") (pinfunction "PI7_B3") (pintype "passive"))
    )
    (net (code "306") (name "Net-(U7B-PI9)") (class "Default")
      (node (ref "R242") (pin "2") (pinfunction "2_2") (pintype "passive"))
      (node (ref "U7") (pin "E2") (pinfunction "PI9_E2") (pintype "passive"))
    )
    (net (code "307") (name "Net-(U7B-PI10)") (class "Default")
      (node (ref "R246") (pin "2") (pinfunction "2_2") (pintype "passive"))
      (node (ref "U7") (pin "F3") (pinfunction "PI10_F3") (pintype "passive"))
    )
    (net (code "308") (name "Net-(U7B-PI14)") (class "Default")
      (node (ref "R220") (pin "2") (pinfunction "2_2") (pintype "passive"))
      (node (ref "U7") (pin "H3") (pinfunction "PI14_H3") (pintype "passive"))
    )
    (net (code "309") (name "VBUS_FS1") (class "Default")
      (node (ref "R255") (pin "1") (pinfunction "1_1") (pintype "passive"))
    )
    (net (code "310") (name "VBUS_FS2") (class "Default")
      (node (ref "R254") (pin "1") (pinfunction "1_1") (pintype "passive"))
    )
  )
)
